# pyControl_breakout_1_2r1.net
KiCad netlist of a schematic drawn in EAGLE
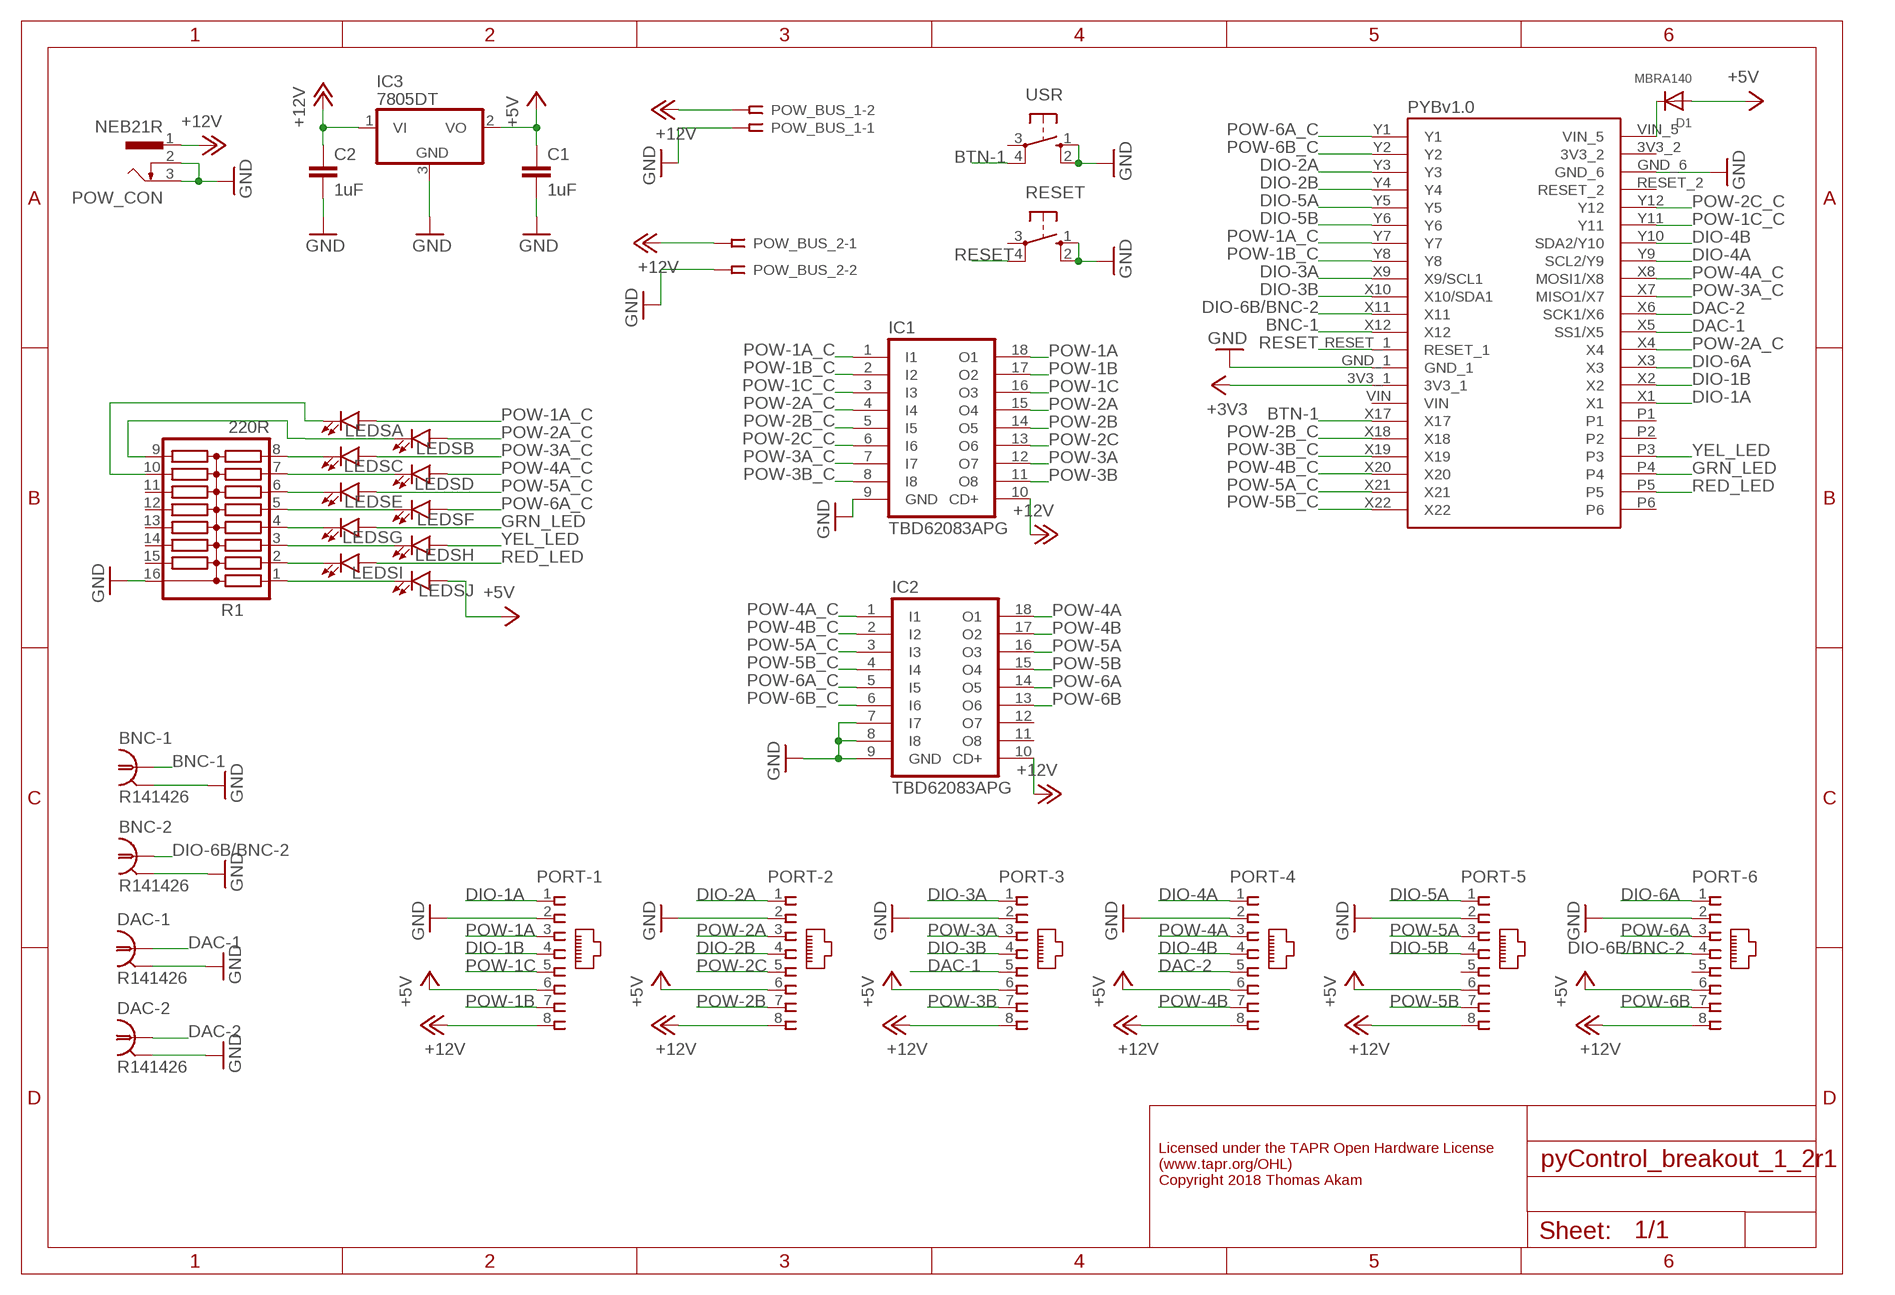
[diagram p0: schematic, sheet 1]

(export (version "E")
  (design (tool "Eeschema 10.0.6"))
  (components
    (comp (ref "BNC-1")
      (value "R141426")
      (footprint "eagle-import:R141426")
      (fields (field (name "MF") "FARNELL") (field (name "MPN") "R141426161"))
      (libsource (lib "eagle-import") (part "R141426"))
    )
    (comp (ref "BNC-2")
      (value "R141426")
      (footprint "eagle-import:R141426")
      (fields (field (name "MF") "FARNELL") (field (name "MPN") "R141426161"))
      (libsource (lib "eagle-import") (part "R141426"))
    )
    (comp (ref "C1")
      (value "1uF")
      (footprint "eagle-import:C1206")
      (libsource (lib "eagle-import") (part "C-EUC1206"))
    )
    (comp (ref "C2")
      (value "1uF")
      (footprint "eagle-import:C1206")
      (libsource (lib "eagle-import") (part "C-EUC1206"))
    )
    (comp (ref "D1")
      (value "MBRA140")
      (footprint "eagle-import:SOD-123")
      (libsource (lib "eagle-import") (part "DIODESOD-123"))
    )
    (comp (ref "DAC-1")
      (value "R141426")
      (footprint "eagle-import:R141426")
      (fields (field (name "MF") "FARNELL") (field (name "MPN") "R141426161"))
      (libsource (lib "eagle-import") (part "R141426"))
    )
    (comp (ref "DAC-2")
      (value "R141426")
      (footprint "eagle-import:R141426")
      (fields (field (name "MF") "FARNELL") (field (name "MPN") "R141426161"))
      (libsource (lib "eagle-import") (part "R141426"))
    )
    (comp (ref "IC1")
      (value "TBD62083APG")
      (footprint "eagle-import:DIL18")
      (libsource (lib "eagle-import") (part "ULN2803A"))
    )
    (comp (ref "IC2")
      (value "TBD62083APG")
      (footprint "eagle-import:DIL18")
      (libsource (lib "eagle-import") (part "ULN2803A"))
    )
    (comp (ref "IC3")
      (value "7805DT")
      (footprint "eagle-import:TO252")
      (libsource (lib "eagle-import") (part "78DT05"))
    )
    (comp (ref "LEDS")
      (value "LED_BARGRAPH_10")
      (footprint "eagle-import:LED_BARGAPH_10")
      (libsource (lib "eagle-import") (part "LED_BARGRAPH_10"))
    )
    (comp (ref "PORT-1")
      (value "RJ45VERTICAL")
      (footprint "eagle-import:RJ45-NO-SHIELD-VERTICAL")
      (libsource (lib "eagle-import") (part "RJ45VERTICAL"))
    )
    (comp (ref "PORT-2")
      (value "RJ45VERTICAL")
      (footprint "eagle-import:RJ45-NO-SHIELD-VERTICAL")
      (libsource (lib "eagle-import") (part "RJ45VERTICAL"))
    )
    (comp (ref "PORT-3")
      (value "RJ45VERTICAL")
      (footprint "eagle-import:RJ45-NO-SHIELD-VERTICAL")
      (libsource (lib "eagle-import") (part "RJ45VERTICAL"))
    )
    (comp (ref "PORT-4")
      (value "RJ45VERTICAL")
      (footprint "eagle-import:RJ45-NO-SHIELD-VERTICAL")
      (libsource (lib "eagle-import") (part "RJ45VERTICAL"))
    )
    (comp (ref "PORT-5")
      (value "RJ45VERTICAL")
      (footprint "eagle-import:RJ45-NO-SHIELD-VERTICAL")
      (libsource (lib "eagle-import") (part "RJ45VERTICAL"))
    )
    (comp (ref "PORT-6")
      (value "RJ45VERTICAL")
      (footprint "eagle-import:RJ45-NO-SHIELD-VERTICAL")
      (libsource (lib "eagle-import") (part "RJ45VERTICAL"))
    )
    (comp (ref "POW_BUS_1")
      (value "SSW-102-02-S-S-RA")
      (footprint "eagle-import:SSW-102-02-S-S-RA")
      (libsource (lib "eagle-import") (part "SSW-102-02-S-S-RA"))
    )
    (comp (ref "POW_BUS_2")
      (value "SSW-102-02-S-S-RA")
      (footprint "eagle-import:SSW-102-02-S-S-RA")
      (libsource (lib "eagle-import") (part "SSW-102-02-S-S-RA"))
    )
    (comp (ref "POW_CON")
      (value "NEB21R")
      (footprint "eagle-import:NEB21R")
      (fields (field (name "MPN") "NEB 21 R"))
      (libsource (lib "eagle-import") (part "NEB21R"))
    )
    (comp (ref "PYBOARD")
      (value "PYBOARD-REDUCED-2")
      (footprint "eagle-import:PYBOARD-REDUCED-2")
      (libsource (lib "eagle-import") (part "PYBOARD-REDUCED-2"))
    )
    (comp (ref "R1")
      (value "220R")
      (footprint "eagle-import:SO16")
      (libsource (lib "eagle-import") (part "2NBS16-15"))
    )
    (comp (ref "RESET")
      (value "40-XX")
      (footprint "eagle-import:B3F-40XX")
      (fields
        (field (name "MF") "OMRON COMPONENTS USA")
        (field (name "MPN") "B3F-4000")
        (field (name "MF_1") "OMRON COMPONENTS USA")
        (field (name "MPN_1") "B3F-4000")
        (field (name "OC_FARNELL") "176434")
        (field (name "OC_NEWARK") "36K3105")
      )
      (libsource (lib "eagle-import") (part "40-XX"))
    )
    (comp (ref "USR")
      (value "40-XX")
      (footprint "eagle-import:B3F-40XX")
      (fields (field (name "MF") "OMRON COMPONENTS USA") (field (name "MPN") "B3F-4000"))
      (libsource (lib "eagle-import") (part "40-XX"))
    )
  )
  (nets
    (net (code "1") (name "+3V3") (class "Default")
      (node (ref "PYBOARD") (pin "3V3_1") (pinfunction "3V3_1_3V3_1") (pintype "bidirectional"))
    )
    (net (code "2") (name "+5V") (class "Default")
      (node (ref "C1") (pin "1") (pinfunction "1_1") (pintype "passive"))
      (node (ref "D1") (pin "A") (pinfunction "A_A") (pintype "passive"))
      (node (ref "IC3") (pin "2") (pinfunction "VO_2") (pintype "passive"))
      (node (ref "LEDS") (pin "10") (pinfunction "A_10") (pintype "passive"))
      (node (ref "PORT-1") (pin "6") (pinfunction "6_6") (pintype "passive"))
      (node (ref "PORT-2") (pin "6") (pinfunction "6_6") (pintype "passive"))
      (node (ref "PORT-3") (pin "6") (pinfunction "6_6") (pintype "passive"))
      (node (ref "PORT-4") (pin "6") (pinfunction "6_6") (pintype "passive"))
      (node (ref "PORT-5") (pin "6") (pinfunction "6_6") (pintype "passive"))
      (node (ref "PORT-6") (pin "6") (pinfunction "6_6") (pintype "passive"))
    )
    (net (code "3") (name "+12V") (class "Default")
      (node (ref "C2") (pin "1") (pinfunction "1_1") (pintype "passive"))
      (node (ref "IC1") (pin "10") (pinfunction "CD+_10") (pintype "passive"))
      (node (ref "IC2") (pin "10") (pinfunction "CD+_10") (pintype "passive"))
      (node (ref "IC3") (pin "1") (pinfunction "VI_1") (pintype "input"))
      (node (ref "PORT-1") (pin "8") (pinfunction "8_8") (pintype "passive"))
      (node (ref "PORT-2") (pin "8") (pinfunction "8_8") (pintype "passive"))
      (node (ref "PORT-3") (pin "8") (pinfunction "8_8") (pintype "passive"))
      (node (ref "PORT-4") (pin "8") (pinfunction "8_8") (pintype "passive"))
      (node (ref "PORT-5") (pin "8") (pinfunction "8_8") (pintype "passive"))
      (node (ref "PORT-6") (pin "8") (pinfunction "8_8") (pintype "passive"))
      (node (ref "POW_BUS_1") (pin "2") (pinfunction "1_2") (pintype "passive"))
      (node (ref "POW_BUS_2") (pin "1") (pinfunction "1_1") (pintype "passive"))
      (node (ref "POW_CON") (pin "1") (pinfunction "1_1") (pintype "passive"))
    )
    (net (code "4") (name "/BNC-1") (class "Default")
      (node (ref "BNC-1") (pin "1") (pinfunction "1_1") (pintype "passive"))
      (node (ref "PYBOARD") (pin "X12") (pinfunction "X12_X12") (pintype "bidirectional"))
    )
    (net (code "5") (name "/BTN-1") (class "Default")
      (node (ref "PYBOARD") (pin "X17") (pinfunction "X17_X17") (pintype "bidirectional"))
      (node (ref "USR") (pin "4") (pinfunction "P1_4") (pintype "passive"))
    )
    (net (code "6") (name "/DAC-1") (class "Default")
      (node (ref "DAC-1") (pin "1") (pinfunction "1_1") (pintype "passive"))
      (node (ref "PORT-3") (pin "5") (pinfunction "5_5") (pintype "passive"))
      (node (ref "PYBOARD") (pin "X5") (pinfunction "SS1/X5_X5") (pintype "bidirectional"))
    )
    (net (code "7") (name "/DAC-2") (class "Default")
      (node (ref "DAC-2") (pin "1") (pinfunction "1_1") (pintype "passive"))
      (node (ref "PORT-4") (pin "5") (pinfunction "5_5") (pintype "passive"))
      (node (ref "PYBOARD") (pin "X6") (pinfunction "SCK1/X6_X6") (pintype "bidirectional"))
    )
    (net (code "8") (name "/DIO-1A") (class "Default")
      (node (ref "PORT-1") (pin "1") (pinfunction "1_1") (pintype "passive"))
      (node (ref "PYBOARD") (pin "X1") (pinfunction "X1_X1") (pintype "bidirectional"))
    )
    (net (code "9") (name "/DIO-1B") (class "Default")
      (node (ref "PORT-1") (pin "4") (pinfunction "4_4") (pintype "passive"))
      (node (ref "PYBOARD") (pin "X2") (pinfunction "X2_X2") (pintype "bidirectional"))
    )
    (net (code "10") (name "/DIO-2A") (class "Default")
      (node (ref "PORT-2") (pin "1") (pinfunction "1_1") (pintype "passive"))
      (node (ref "PYBOARD") (pin "Y3") (pinfunction "Y3_Y3") (pintype "bidirectional"))
    )
    (net (code "11") (name "/DIO-2B") (class "Default")
      (node (ref "PORT-2") (pin "4") (pinfunction "4_4") (pintype "passive"))
      (node (ref "PYBOARD") (pin "Y4") (pinfunction "Y4_Y4") (pintype "bidirectional"))
    )
    (net (code "12") (name "/DIO-3A") (class "Default")
      (node (ref "PORT-3") (pin "1") (pinfunction "1_1") (pintype "passive"))
      (node (ref "PYBOARD") (pin "X9") (pinfunction "X9/SCL1_X9") (pintype "bidirectional"))
    )
    (net (code "13") (name "/DIO-3B") (class "Default")
      (node (ref "PORT-3") (pin "4") (pinfunction "4_4") (pintype "passive"))
      (node (ref "PYBOARD") (pin "X10") (pinfunction "X10/SDA1_X10") (pintype "bidirectional"))
    )
    (net (code "14") (name "/DIO-4A") (class "Default")
      (node (ref "PORT-4") (pin "1") (pinfunction "1_1") (pintype "passive"))
      (node (ref "PYBOARD") (pin "Y9") (pinfunction "SCL2/Y9_Y9") (pintype "bidirectional"))
    )
    (net (code "15") (name "/DIO-4B") (class "Default")
      (node (ref "PORT-4") (pin "4") (pinfunction "4_4") (pintype "passive"))
      (node (ref "PYBOARD") (pin "Y10") (pinfunction "SDA2/Y10_Y10") (pintype "bidirectional"))
    )
    (net (code "16") (name "/DIO-5A") (class "Default")
      (node (ref "PORT-5") (pin "1") (pinfunction "1_1") (pintype "passive"))
      (node (ref "PYBOARD") (pin "Y5") (pinfunction "Y5_Y5") (pintype "bidirectional"))
    )
    (net (code "17") (name "/DIO-5B") (class "Default")
      (node (ref "PORT-5") (pin "4") (pinfunction "4_4") (pintype "passive"))
      (node (ref "PYBOARD") (pin "Y6") (pinfunction "Y6_Y6") (pintype "bidirectional"))
    )
    (net (code "18") (name "/DIO-6A") (class "Default")
      (node (ref "PORT-6") (pin "1") (pinfunction "1_1") (pintype "passive"))
      (node (ref "PYBOARD") (pin "X3") (pinfunction "X3_X3") (pintype "bidirectional"))
    )
    (net (code "19") (name "/DIO-6B{slash}BNC-2") (class "Default")
      (node (ref "BNC-2") (pin "1") (pinfunction "1_1") (pintype "passive"))
      (node (ref "PORT-6") (pin "4") (pinfunction "4_4") (pintype "passive"))
      (node (ref "PYBOARD") (pin "X11") (pinfunction "X11_X11") (pintype "bidirectional"))
    )
    (net (code "20") (name "/GRN_LED") (class "Default")
      (node (ref "LEDS") (pin "7") (pinfunction "A_7") (pintype "passive"))
      (node (ref "PYBOARD") (pin "P4") (pinfunction "P4_P4") (pintype "bidirectional"))
    )
    (net (code "21") (name "/POW-1A") (class "Default")
      (node (ref "IC1") (pin "18") (pinfunction "O1_18") (pintype "open_collector"))
      (node (ref "PORT-1") (pin "3") (pinfunction "3_3") (pintype "passive"))
    )
    (net (code "22") (name "/POW-1A_C") (class "Default")
      (node (ref "IC1") (pin "1") (pinfunction "I1_1") (pintype "input"))
      (node (ref "LEDS") (pin "1") (pinfunction "A_1") (pintype "passive"))
      (node (ref "PYBOARD") (pin "Y7") (pinfunction "Y7_Y7") (pintype "bidirectional"))
    )
    (net (code "23") (name "/POW-1B") (class "Default")
      (node (ref "IC1") (pin "17") (pinfunction "O2_17") (pintype "open_collector"))
      (node (ref "PORT-1") (pin "7") (pinfunction "7_7") (pintype "passive"))
    )
    (net (code "24") (name "/POW-1B_C") (class "Default")
      (node (ref "IC1") (pin "2") (pinfunction "I2_2") (pintype "input"))
      (node (ref "PYBOARD") (pin "Y8") (pinfunction "Y8_Y8") (pintype "bidirectional"))
    )
    (net (code "25") (name "/POW-1C") (class "Default")
      (node (ref "IC1") (pin "16") (pinfunction "O3_16") (pintype "open_collector"))
      (node (ref "PORT-1") (pin "5") (pinfunction "5_5") (pintype "passive"))
    )
    (net (code "26") (name "/POW-1C_C") (class "Default")
      (node (ref "IC1") (pin "3") (pinfunction "I3_3") (pintype "input"))
      (node (ref "PYBOARD") (pin "Y11") (pinfunction "Y11_Y11") (pintype "bidirectional"))
    )
    (net (code "27") (name "/POW-2A") (class "Default")
      (node (ref "IC1") (pin "15") (pinfunction "O4_15") (pintype "open_collector"))
      (node (ref "PORT-2") (pin "3") (pinfunction "3_3") (pintype "passive"))
    )
    (net (code "28") (name "/POW-2A_C") (class "Default")
      (node (ref "IC1") (pin "4") (pinfunction "I4_4") (pintype "input"))
      (node (ref "LEDS") (pin "2") (pinfunction "A_2") (pintype "passive"))
      (node (ref "PYBOARD") (pin "X4") (pinfunction "X4_X4") (pintype "bidirectional"))
    )
    (net (code "29") (name "/POW-2B") (class "Default")
      (node (ref "IC1") (pin "14") (pinfunction "O5_14") (pintype "open_collector"))
      (node (ref "PORT-2") (pin "7") (pinfunction "7_7") (pintype "passive"))
    )
    (net (code "30") (name "/POW-2B_C") (class "Default")
      (node (ref "IC1") (pin "5") (pinfunction "I5_5") (pintype "input"))
      (node (ref "PYBOARD") (pin "X18") (pinfunction "X18_X18") (pintype "bidirectional"))
    )
    (net (code "31") (name "/POW-2C") (class "Default")
      (node (ref "IC1") (pin "13") (pinfunction "O6_13") (pintype "open_collector"))
      (node (ref "PORT-2") (pin "5") (pinfunction "5_5") (pintype "passive"))
    )
    (net (code "32") (name "/POW-2C_C") (class "Default")
      (node (ref "IC1") (pin "6") (pinfunction "I6_6") (pintype "input"))
      (node (ref "PYBOARD") (pin "Y12") (pinfunction "Y12_Y12") (pintype "bidirectional"))
    )
    (net (code "33") (name "/POW-3A") (class "Default")
      (node (ref "IC1") (pin "12") (pinfunction "O7_12") (pintype "open_collector"))
      (node (ref "PORT-3") (pin "3") (pinfunction "3_3") (pintype "passive"))
    )
    (net (code "34") (name "/POW-3A_C") (class "Default")
      (node (ref "IC1") (pin "7") (pinfunction "I7_7") (pintype "input"))
      (node (ref "LEDS") (pin "3") (pinfunction "A_3") (pintype "passive"))
      (node (ref "PYBOARD") (pin "X7") (pinfunction "MISO1/X7_X7") (pintype "bidirectional"))
    )
    (net (code "35") (name "/POW-3B") (class "Default")
      (node (ref "IC1") (pin "11") (pinfunction "O8_11") (pintype "open_collector"))
      (node (ref "PORT-3") (pin "7") (pinfunction "7_7") (pintype "passive"))
    )
    (net (code "36") (name "/POW-3B_C") (class "Default")
      (node (ref "IC1") (pin "8") (pinfunction "I8_8") (pintype "input"))
      (node (ref "PYBOARD") (pin "X19") (pinfunction "X19_X19") (pintype "bidirectional"))
    )
    (net (code "37") (name "/POW-4A") (class "Default")
      (node (ref "IC2") (pin "18") (pinfunction "O1_18") (pintype "open_collector"))
      (node (ref "PORT-4") (pin "3") (pinfunction "3_3") (pintype "passive"))
    )
    (net (code "38") (name "/POW-4A_C") (class "Default")
      (node (ref "IC2") (pin "1") (pinfunction "I1_1") (pintype "input"))
      (node (ref "LEDS") (pin "4") (pinfunction "A_4") (pintype "passive"))
      (node (ref "PYBOARD") (pin "X8") (pinfunction "MOSI1/X8_X8") (pintype "bidirectional"))
    )
    (net (code "39") (name "/POW-4B") (class "Default")
      (node (ref "IC2") (pin "17") (pinfunction "O2_17") (pintype "open_collector"))
      (node (ref "PORT-4") (pin "7") (pinfunction "7_7") (pintype "passive"))
    )
    (net (code "40") (name "/POW-4B_C") (class "Default")
      (node (ref "IC2") (pin "2") (pinfunction "I2_2") (pintype "input"))
      (node (ref "PYBOARD") (pin "X20") (pinfunction "X20_X20") (pintype "bidirectional"))
    )
    (net (code "41") (name "/POW-5A") (class "Default")
      (node (ref "IC2") (pin "16") (pinfunction "O3_16") (pintype "open_collector"))
      (node (ref "PORT-5") (pin "3") (pinfunction "3_3") (pintype "passive"))
    )
    (net (code "42") (name "/POW-5A_C") (class "Default")
      (node (ref "IC2") (pin "3") (pinfunction "I3_3") (pintype "input"))
      (node (ref "LEDS") (pin "5") (pinfunction "A_5") (pintype "passive"))
      (node (ref "PYBOARD") (pin "X21") (pinfunction "X21_X21") (pintype "bidirectional"))
    )
    (net (code "43") (name "/POW-5B") (class "Default")
      (node (ref "IC2") (pin "15") (pinfunction "O4_15") (pintype "open_collector"))
      (node (ref "PORT-5") (pin "7") (pinfunction "7_7") (pintype "passive"))
    )
    (net (code "44") (name "/POW-5B_C") (class "Default")
      (node (ref "IC2") (pin "4") (pinfunction "I4_4") (pintype "input"))
      (node (ref "PYBOARD") (pin "X22") (pinfunction "X22_X22") (pintype "bidirectional"))
    )
    (net (code "45") (name "/POW-6A") (class "Default")
      (node (ref "IC2") (pin "14") (pinfunction "O5_14") (pintype "open_collector"))
      (node (ref "PORT-6") (pin "3") (pinfunction "3_3") (pintype "passive"))
    )
    (net (code "46") (name "/POW-6A_C") (class "Default")
      (node (ref "IC2") (pin "5") (pinfunction "I5_5") (pintype "input"))
      (node (ref "LEDS") (pin "6") (pinfunction "A_6") (pintype "passive"))
      (node (ref "PYBOARD") (pin "Y1") (pinfunction "Y1_Y1") (pintype "bidirectional"))
    )
    (net (code "47") (name "/POW-6B") (class "Default")
      (node (ref "IC2") (pin "13") (pinfunction "O6_13") (pintype "open_collector"))
      (node (ref "PORT-6") (pin "7") (pinfunction "7_7") (pintype "passive"))
    )
    (net (code "48") (name "/POW-6B_C") (class "Default")
      (node (ref "IC2") (pin "6") (pinfunction "I6_6") (pintype "input"))
      (node (ref "PYBOARD") (pin "Y2") (pinfunction "Y2_Y2") (pintype "bidirectional"))
    )
    (net (code "49") (name "/RED_LED") (class "Default")
      (node (ref "LEDS") (pin "9") (pinfunction "A_9") (pintype "passive"))
      (node (ref "PYBOARD") (pin "P5") (pinfunction "P5_P5") (pintype "bidirectional"))
    )
    (net (code "50") (name "/RESET") (class "Default")
      (node (ref "PYBOARD") (pin "RESET_1") (pinfunction "RESET_1_RESET_1") (pintype "bidirectional"))
      (node (ref "RESET") (pin "4") (pinfunction "P1_4") (pintype "passive"))
    )
    (net (code "51") (name "/YEL_LED") (class "Default")
      (node (ref "LEDS") (pin "8") (pinfunction "A_8") (pintype "passive"))
      (node (ref "PYBOARD") (pin "P3") (pinfunction "P3_P3") (pintype "bidirectional"))
    )
    (net (code "52") (name "GND") (class "Default")
      (node (ref "BNC-1") (pin "2") (pinfunction "GND_2") (pintype "power_in"))
      (node (ref "BNC-2") (pin "2") (pinfunction "GND_2") (pintype "power_in"))
      (node (ref "C1") (pin "2") (pinfunction "2_2") (pintype "passive"))
      (node (ref "C2") (pin "2") (pinfunction "2_2") (pintype "passive"))
      (node (ref "DAC-1") (pin "2") (pinfunction "GND_2") (pintype "power_in"))
      (node (ref "DAC-2") (pin "2") (pinfunction "GND_2") (pintype "power_in"))
      (node (ref "IC1") (pin "9") (pinfunction "GND_9") (pintype "power_in"))
      (node (ref "IC2") (pin "7") (pinfunction "I7_7") (pintype "input"))
      (node (ref "IC2") (pin "8") (pinfunction "I8_8") (pintype "input"))
      (node (ref "IC2") (pin "9") (pinfunction "GND_9") (pintype "power_in"))
      (node (ref "IC3") (pin "3") (pinfunction "GND_3") (pintype "passive"))
      (node (ref "PORT-1") (pin "2") (pinfunction "2_2") (pintype "passive"))
      (node (ref "PORT-2") (pin "2") (pinfunction "2_2") (pintype "passive"))
      (node (ref "PORT-3") (pin "2") (pinfunction "2_2") (pintype "passive"))
      (node (ref "PORT-4") (pin "2") (pinfunction "2_2") (pintype "passive"))
      (node (ref "PORT-5") (pin "2") (pinfunction "2_2") (pintype "passive"))
      (node (ref "PORT-6") (pin "2") (pinfunction "2_2") (pintype "passive"))
      (node (ref "POW_BUS_1") (pin "1") (pinfunction "1_1") (pintype "passive"))
      (node (ref "POW_BUS_2") (pin "2") (pinfunction "1_2") (pintype "passive"))
      (node (ref "POW_CON") (pin "2") (pinfunction "2_2") (pintype "passive"))
      (node (ref "POW_CON") (pin "3") (pinfunction "3_3") (pintype "passive"))
      (node (ref "PYBOARD") (pin "GND_1") (pinfunction "GND_1_GND_1") (pintype "bidirectional"))
      (node (ref "PYBOARD") (pin "GND_6") (pinfunction "GND_6_GND_6") (pintype "bidirectional"))
      (node (ref "R1") (pin "16") (pinfunction "16_16") (pintype "passive"))
      (node (ref "RESET") (pin "1") (pinfunction "S_1") (pintype "passive"))
      (node (ref "RESET") (pin "2") (pinfunction "S1_2") (pintype "passive"))
      (node (ref "USR") (pin "1") (pinfunction "S_1") (pintype "passive"))
      (node (ref "USR") (pin "2") (pinfunction "S1_2") (pintype "passive"))
    )
    (net (code "53") (name "Net-(D1-PadC)") (class "Default")
      (node (ref "D1") (pin "C") (pinfunction "C_C") (pintype "passive"))
      (node (ref "PYBOARD") (pin "VIN_5") (pinfunction "VIN_5_VIN_5") (pintype "bidirectional"))
    )
    (net (code "54") (name "Net-(LEDSA-C)") (class "Default")
      (node (ref "LEDS") (pin "20") (pinfunction "C_20") (pintype "passive"))
      (node (ref "R1") (pin "10") (pinfunction "10_10") (pintype "passive"))
    )
    (net (code "55") (name "Net-(LEDSB-C)") (class "Default")
      (node (ref "LEDS") (pin "19") (pinfunction "C_19") (pintype "passive"))
      (node (ref "R1") (pin "9") (pinfunction "9_9") (pintype "passive"))
    )
    (net (code "56") (name "Net-(LEDSC-C)") (class "Default")
      (node (ref "LEDS") (pin "18") (pinfunction "C_18") (pintype "passive"))
      (node (ref "R1") (pin "8") (pinfunction "8_8") (pintype "passive"))
    )
    (net (code "57") (name "Net-(LEDSD-C)") (class "Default")
      (node (ref "LEDS") (pin "17") (pinfunction "C_17") (pintype "passive"))
      (node (ref "R1") (pin "7") (pinfunction "7_7") (pintype "passive"))
    )
    (net (code "58") (name "Net-(LEDSE-C)") (class "Default")
      (node (ref "LEDS") (pin "16") (pinfunction "C_16") (pintype "passive"))
      (node (ref "R1") (pin "6") (pinfunction "6_6") (pintype "passive"))
    )
    (net (code "59") (name "Net-(LEDSF-C)") (class "Default")
      (node (ref "LEDS") (pin "15") (pinfunction "C_15") (pintype "passive"))
      (node (ref "R1") (pin "5") (pinfunction "5_5") (pintype "passive"))
    )
    (net (code "60") (name "Net-(LEDSG-C)") (class "Default")
      (node (ref "LEDS") (pin "14") (pinfunction "C_14") (pintype "passive"))
      (node (ref "R1") (pin "4") (pinfunction "4_4") (pintype "passive"))
    )
    (net (code "61") (name "Net-(LEDSH-C)") (class "Default")
      (node (ref "LEDS") (pin "13") (pinfunction "C_13") (pintype "passive"))
      (node (ref "R1") (pin "3") (pinfunction "3_3") (pintype "passive"))
    )
    (net (code "62") (name "Net-(LEDSI-C)") (class "Default")
      (node (ref "LEDS") (pin "12") (pinfunction "C_12") (pintype "passive"))
      (node (ref "R1") (pin "2") (pinfunction "2_2") (pintype "passive"))
    )
    (net (code "63") (name "Net-(LEDSJ-C)") (class "Default")
      (node (ref "LEDS") (pin "11") (pinfunction "C_11") (pintype "passive"))
      (node (ref "R1") (pin "1") (pinfunction "1_1") (pintype "passive"))
    )
    (net (code "64") (name "unconnected-(IC2-O7-Pad12)") (class "Default")
      (node (ref "IC2") (pin "12") (pinfunction "O7_12") (pintype "open_collector"))
    )
    (net (code "65") (name "unconnected-(IC2-O8-Pad11)") (class "Default")
      (node (ref "IC2") (pin "11") (pinfunction "O8_11") (pintype "open_collector"))
    )
    (net (code "66") (name "unconnected-(PORT-5-Pad5)") (class "Default")
      (node (ref "PORT-5") (pin "5") (pinfunction "5_5") (pintype "passive"))
    )
    (net (code "67") (name "unconnected-(PORT-6-Pad5)") (class "Default")
      (node (ref "PORT-6") (pin "5") (pinfunction "5_5") (pintype "passive"))
    )
    (net (code "68") (name "unconnected-(PYBOARD-Pad3V3_2)") (class "Default")
      (node (ref "PYBOARD") (pin "3V3_2") (pinfunction "3V3_2_3V3_2") (pintype "bidirectional"))
    )
    (net (code "69") (name "unconnected-(PYBOARD-PadP1)") (class "Default")
      (node (ref "PYBOARD") (pin "P1") (pinfunction "P1_P1") (pintype "bidirectional"))
    )
    (net (code "70") (name "unconnected-(PYBOARD-PadP2)") (class "Default")
      (node (ref "PYBOARD") (pin "P2") (pinfunction "P2_P2") (pintype "bidirectional"))
    )
    (net (code "71") (name "unconnected-(PYBOARD-PadP6)") (class "Default")
      (node (ref "PYBOARD") (pin "P6") (pinfunction "P6_P6") (pintype "bidirectional"))
    )
    (net (code "72") (name "unconnected-(PYBOARD-PadRESET_2)") (class "Default")
      (node (ref "PYBOARD") (pin "RESET_2") (pinfunction "RESET_2_RESET_2") (pintype "bidirectional"))
    )
    (net (code "73") (name "unconnected-(PYBOARD-PadVIN)") (class "Default")
      (node (ref "PYBOARD") (pin "VIN") (pinfunction "VIN_VIN") (pintype "bidirectional"))
    )
    (net (code "74") (name "unconnected-(R1-Pad11)") (class "Default")
      (node (ref "R1") (pin "11") (pinfunction "11_11") (pintype "passive"))
    )
    (net (code "75") (name "unconnected-(R1-Pad12)") (class "Default")
      (node (ref "R1") (pin "12") (pinfunction "12_12") (pintype "passive"))
    )
    (net (code "76") (name "unconnected-(R1-Pad13)") (class "Default")
      (node (ref "R1") (pin "13") (pinfunction "13_13") (pintype "passive"))
    )
    (net (code "77") (name "unconnected-(R1-Pad14)") (class "Default")
      (node (ref "R1") (pin "14") (pinfunction "14_14") (pintype "passive"))
    )
    (net (code "78") (name "unconnected-(R1-Pad15)") (class "Default")
      (node (ref "R1") (pin "15") (pinfunction "15_15") (pintype "passive"))
    )
    (net (code "79") (name "unconnected-(RESET-P-Pad3)") (class "Default")
      (node (ref "RESET") (pin "3") (pinfunction "P_3") (pintype "passive"))
    )
    (net (code "80") (name "unconnected-(USR-P-Pad3)") (class "Default")
      (node (ref "USR") (pin "3") (pinfunction "P_3") (pintype "passive"))
    )
  )
)
